# FET_1_and_FET_2_Isolated_Gate_Drive.net
KiCad netlist of a schematic drawn in Altium Designer
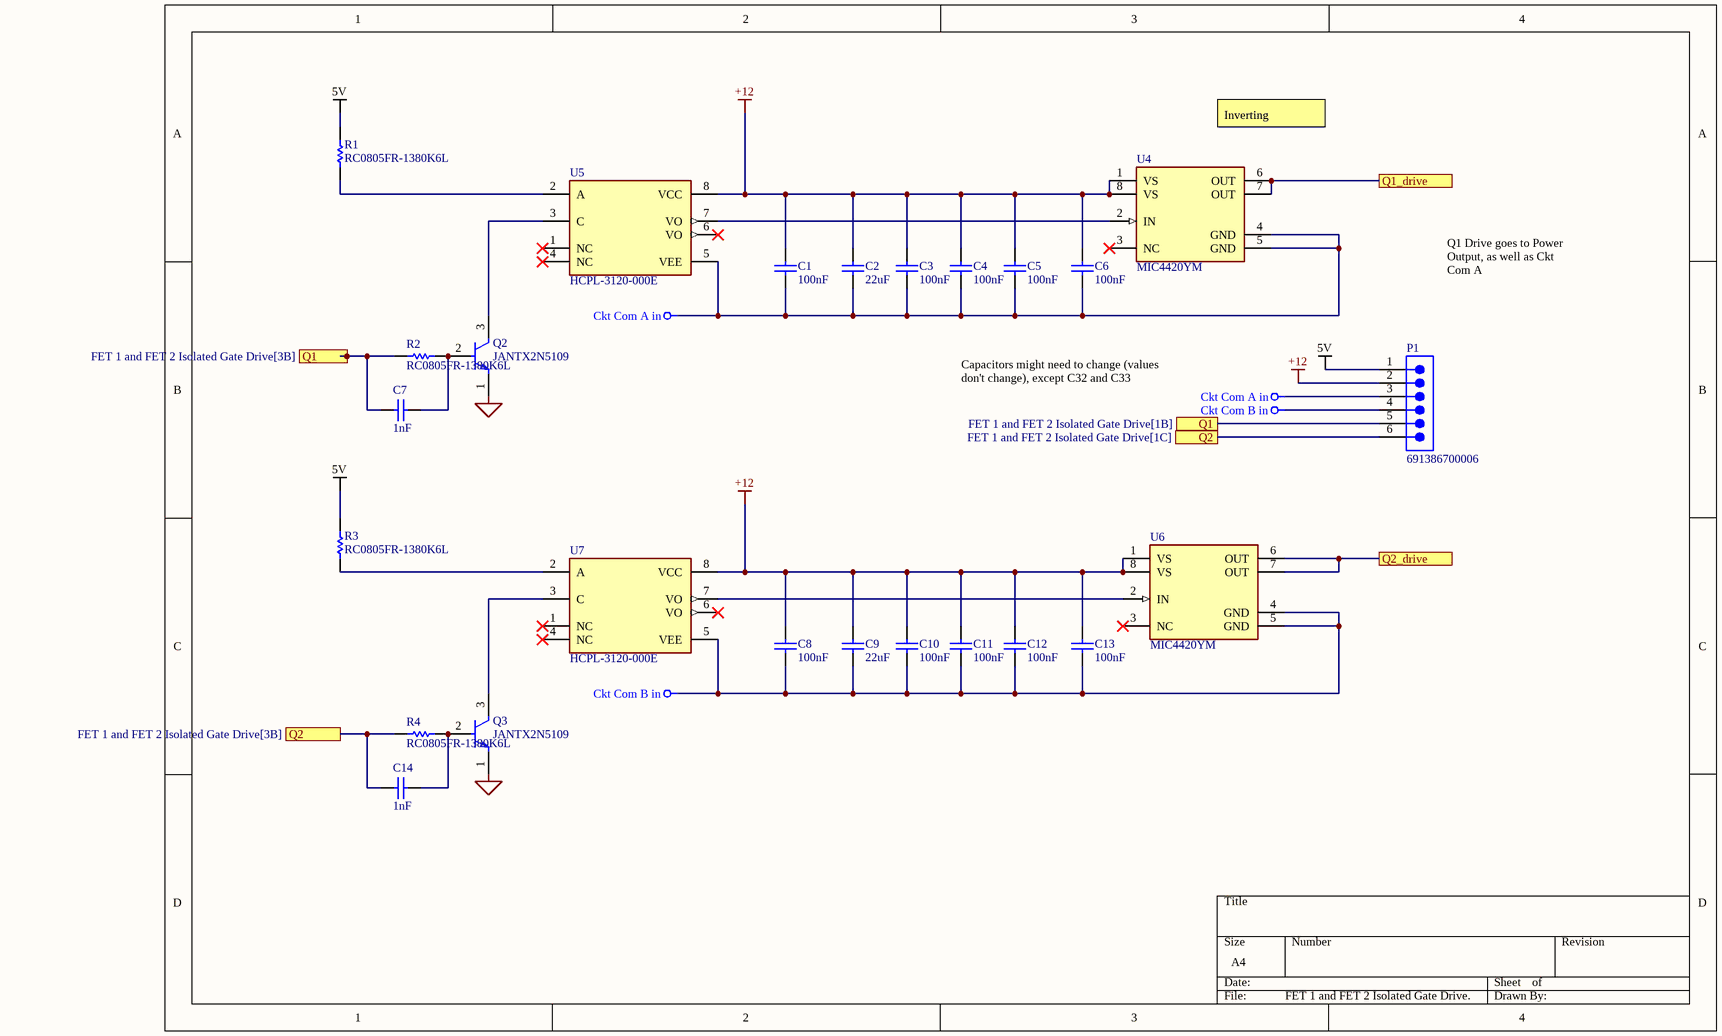
[diagram p0: FET 1 and FET 2 Isolated Gate Drive.SchDoc]

(export (version "E")
  (design (tool "Eeschema 10.0.6"))
  (components
    (comp (ref "C1")
      (value "100nF")
      (footprint "CAPC2013X140X50ML20T25")
      (fields
        (field (name "PART NUMBER") "0805DD104KAT2A")
        (field (name "MANUFACTURER") "AVX Interconnect / Elco")
      )
      (libsource (lib "Altium Content Vault") (part "CAP"))
    )
    (comp (ref "C2")
      (value "22uF")
      (footprint "CAPC0805(2012)145_L")
      (description "CAP 22uF 6.3V ±10% 0805 (2012 Metric) Thickness 1.45mm SMD")
      (fields (field (name "TOLERANCE") "Â±10%"))
      (libsource (lib "Altium Content Vault") (part "CAP"))
    )
    (comp (ref "C3")
      (value "100nF")
      (footprint "CAPC2013X140X50ML20T25")
      (fields
        (field (name "PART NUMBER") "0805DD104KAT2A")
        (field (name "MANUFACTURER") "AVX Interconnect / Elco")
      )
      (libsource (lib "Altium Content Vault") (part "CAP"))
    )
    (comp (ref "C4")
      (value "100nF")
      (footprint "CAPC2013X140X50ML20T25")
      (fields
        (field (name "PART NUMBER") "0805DD104KAT2A")
        (field (name "MANUFACTURER") "AVX Interconnect / Elco")
      )
      (libsource (lib "Altium Content Vault") (part "CAP"))
    )
    (comp (ref "C5")
      (value "100nF")
      (footprint "CAPC2013X140X50ML20T25")
      (fields
        (field (name "PART NUMBER") "0805DD104KAT2A")
        (field (name "MANUFACTURER") "AVX Interconnect / Elco")
      )
      (libsource (lib "Altium Content Vault") (part "CAP"))
    )
    (comp (ref "C6")
      (value "100nF")
      (footprint "CAPC2013X140X50ML20T25")
      (fields
        (field (name "PART NUMBER") "0805DD104KAT2A")
        (field (name "MANUFACTURER") "AVX Interconnect / Elco")
      )
      (libsource (lib "Altium Content Vault") (part "CAP"))
    )
    (comp (ref "C7")
      (value "1nF")
      (footprint "CAPC2013X145X50LL20T20")
      (fields (field (name "PART NUMBER") "VJ0805Y102JXQPW1BC") (field (name "MANUFACTURER") "Vitramon"))
      (libsource (lib "Altium Content Vault") (part "CAP"))
    )
    (comp (ref "C8")
      (value "100nF")
      (footprint "CAPC2013X140X50ML20T25")
      (fields
        (field (name "PART NUMBER") "0805DD104KAT2A")
        (field (name "MANUFACTURER") "AVX Interconnect / Elco")
      )
      (libsource (lib "Altium Content Vault") (part "CAP"))
    )
    (comp (ref "C9")
      (value "22uF")
      (footprint "CAPC0805(2012)145_L")
      (description "CAP 22uF 6.3V ±10% 0805 (2012 Metric) Thickness 1.45mm SMD")
      (fields (field (name "TOLERANCE") "Â±10%"))
      (libsource (lib "Altium Content Vault") (part "CAP"))
    )
    (comp (ref "C10")
      (value "100nF")
      (footprint "CAPC2013X140X50ML20T25")
      (fields
        (field (name "PART NUMBER") "0805DD104KAT2A")
        (field (name "MANUFACTURER") "AVX Interconnect / Elco")
      )
      (libsource (lib "Altium Content Vault") (part "CAP"))
    )
    (comp (ref "C11")
      (value "100nF")
      (footprint "CAPC2013X140X50ML20T25")
      (fields
        (field (name "PART NUMBER") "0805DD104KAT2A")
        (field (name "MANUFACTURER") "AVX Interconnect / Elco")
      )
      (libsource (lib "Altium Content Vault") (part "CAP"))
    )
    (comp (ref "C12")
      (value "100nF")
      (footprint "CAPC2013X140X50ML20T25")
      (fields
        (field (name "PART NUMBER") "0805DD104KAT2A")
        (field (name "MANUFACTURER") "AVX Interconnect / Elco")
      )
      (libsource (lib "Altium Content Vault") (part "CAP"))
    )
    (comp (ref "C13")
      (value "100nF")
      (footprint "CAPC2013X140X50ML20T25")
      (fields
        (field (name "PART NUMBER") "0805DD104KAT2A")
        (field (name "MANUFACTURER") "AVX Interconnect / Elco")
      )
      (libsource (lib "Altium Content Vault") (part "CAP"))
    )
    (comp (ref "C14")
      (value "1nF")
      (footprint "CAPC2013X145X50LL20T20")
      (fields (field (name "PART NUMBER") "VJ0805Y102JXQPW1BC") (field (name "MANUFACTURER") "Vitramon"))
      (libsource (lib "Altium Content Vault") (part "CAP"))
    )
    (comp (ref "P1")
      (value "691386700006")
      (footprint "691386700006")
      (description "Terminal Block, 5.00MM, Male Pcb Horizontal/vertical Cab Divisible, 6 Pins")
      (fields (field (name "VOLTAGE") "300V"))
      (libsource (lib "Altium Content Vault") (part "TBL - 1R - 06P - Male"))
    )
    (comp (ref "Q2")
      (value "JANTX2N5109")
      (footprint "FP-TO-39-MFG")
      (description "TRANS NPN TO39")
      (libsource (lib "Altium Content Vault") (part "a64cbfbad643015290886283bc510aa"))
    )
    (comp (ref "Q3")
      (value "JANTX2N5109")
      (footprint "FP-TO-39-MFG")
      (description "TRANS NPN TO39")
      (libsource (lib "Altium Content Vault") (part "a64cbfbad643015290886283bc510aa"))
    )
    (comp (ref "R1")
      (value "RC0805FR-1380K6L")
      (footprint "RESC2013X60X35NL10T20")
      (fields (field (name "MANUFACTURER") "Yageo"))
      (libsource (lib "Altium Content Vault") (part "RES"))
    )
    (comp (ref "R2")
      (value "RC0805FR-1380K6L")
      (footprint "RESC2013X60X35NL10T20")
      (fields (field (name "MANUFACTURER") "Yageo"))
      (libsource (lib "Altium Content Vault") (part "RES"))
    )
    (comp (ref "R3")
      (value "RC0805FR-1380K6L")
      (footprint "RESC2013X60X35NL10T20")
      (fields (field (name "MANUFACTURER") "Yageo"))
      (libsource (lib "Altium Content Vault") (part "RES"))
    )
    (comp (ref "R4")
      (value "RC0805FR-1380K6L")
      (footprint "RESC2013X60X35NL10T20")
      (fields (field (name "MANUFACTURER") "Yageo"))
      (libsource (lib "Altium Content Vault") (part "RES"))
    )
    (comp (ref "U4")
      (value "MIC4420YM")
      (footprint "FP-SOICN-8LD-PL-1-IPC_C")
      (description "IC GATE DRVR LOW-SIDE 8SOIC")
      (libsource (lib "Altium Content Vault") (part "59696dd0ae0f4050f2c9023f300317a"))
    )
    (comp (ref "U5")
      (value "HCPL-3120-000E")
      (footprint "FP-DIP-8-MFG")
      (description "OPTOISO 3.75KV 1CH GATE DVR 8DIP")
      (fields
        (field (name "MANUFACTURER") "Broadcom")
        (field (name "OCTOPART") "https://octopart.com/hcpl-3120-000e-broadcom-71128428")
      )
      (libsource (lib "Altium Content Vault") (part "c721bc5cd0517253f59fa39a191c1e6"))
    )
    (comp (ref "U6")
      (value "MIC4420YM")
      (footprint "FP-SOICN-8LD-PL-1-IPC_C")
      (description "IC GATE DRVR LOW-SIDE 8SOIC")
      (libsource (lib "Altium Content Vault") (part "59696dd0ae0f4050f2c9023f300317a"))
    )
    (comp (ref "U7")
      (value "HCPL-3120-000E")
      (footprint "FP-DIP-8-MFG")
      (description "OPTOISO 3.75KV 1CH GATE DVR 8DIP")
      (fields
        (field (name "MANUFACTURER") "Broadcom")
        (field (name "OCTOPART") "https://octopart.com/hcpl-3120-000e-broadcom-71128428")
      )
      (libsource (lib "Altium Content Vault") (part "c721bc5cd0517253f59fa39a191c1e6"))
    )
  )
  (nets
    (net (code "1") (name "+12") (class "Default")
      (node (ref "C1") (pin "2") (pinfunction "2_2") (pintype "passive"))
      (node (ref "C10") (pin "2") (pinfunction "2_2") (pintype "passive"))
      (node (ref "C11") (pin "2") (pinfunction "2_2") (pintype "passive"))
      (node (ref "C12") (pin "2") (pinfunction "2_2") (pintype "passive"))
      (node (ref "C13") (pin "2") (pinfunction "2_2") (pintype "passive"))
      (node (ref "C2") (pin "2") (pinfunction "2_2") (pintype "passive"))
      (node (ref "C3") (pin "2") (pinfunction "2_2") (pintype "passive"))
      (node (ref "C4") (pin "2") (pinfunction "2_2") (pintype "passive"))
      (node (ref "C5") (pin "2") (pinfunction "2_2") (pintype "passive"))
      (node (ref "C6") (pin "2") (pinfunction "2_2") (pintype "passive"))
      (node (ref "C8") (pin "2") (pinfunction "2_2") (pintype "passive"))
      (node (ref "C9") (pin "2") (pinfunction "2_2") (pintype "passive"))
      (node (ref "P1") (pin "2") (pinfunction "2_2") (pintype "passive"))
      (node (ref "U4") (pin "1") (pinfunction "VS_1") (pintype "power_in"))
      (node (ref "U4") (pin "8") (pinfunction "VS_8") (pintype "power_in"))
      (node (ref "U5") (pin "8") (pinfunction "VCC_8") (pintype "power_in"))
      (node (ref "U6") (pin "1") (pinfunction "VS_1") (pintype "power_in"))
      (node (ref "U6") (pin "8") (pinfunction "VS_8") (pintype "power_in"))
      (node (ref "U7") (pin "8") (pinfunction "VCC_8") (pintype "power_in"))
    )
    (net (code "2") (name "/Q1") (class "Default")
      (node (ref "C7") (pin "1") (pinfunction "1_1") (pintype "passive"))
      (node (ref "P1") (pin "5") (pinfunction "5_5") (pintype "passive"))
      (node (ref "R2") (pin "2") (pinfunction "2_2") (pintype "passive"))
    )
    (net (code "3") (name "/Q1_drive") (class "Default")
      (node (ref "U4") (pin "6") (pinfunction "OUT_6") (pintype "passive"))
      (node (ref "U4") (pin "7") (pinfunction "OUT_7") (pintype "passive"))
    )
    (net (code "4") (name "/Q2") (class "Default")
      (node (ref "C14") (pin "1") (pinfunction "1_1") (pintype "passive"))
      (node (ref "P1") (pin "6") (pinfunction "6_6") (pintype "passive"))
      (node (ref "R4") (pin "2") (pinfunction "2_2") (pintype "passive"))
    )
    (net (code "5") (name "/Q2_drive") (class "Default")
      (node (ref "U6") (pin "6") (pinfunction "OUT_6") (pintype "passive"))
      (node (ref "U6") (pin "7") (pinfunction "OUT_7") (pintype "passive"))
    )
    (net (code "6") (name "5V") (class "Default")
      (node (ref "P1") (pin "1") (pinfunction "1_1") (pintype "passive"))
      (node (ref "R1") (pin "2") (pinfunction "2_2") (pintype "passive"))
      (node (ref "R3") (pin "2") (pinfunction "2_2") (pintype "passive"))
    )
    (net (code "7") (name "Ckt Com A in") (class "Default")
      (node (ref "C1") (pin "1") (pinfunction "1_1") (pintype "passive"))
      (node (ref "C2") (pin "1") (pinfunction "1_1") (pintype "passive"))
      (node (ref "C3") (pin "1") (pinfunction "1_1") (pintype "passive"))
      (node (ref "C4") (pin "1") (pinfunction "1_1") (pintype "passive"))
      (node (ref "C5") (pin "1") (pinfunction "1_1") (pintype "passive"))
      (node (ref "C6") (pin "1") (pinfunction "1_1") (pintype "passive"))
      (node (ref "P1") (pin "3") (pinfunction "3_3") (pintype "passive"))
      (node (ref "U4") (pin "4") (pinfunction "GND_4") (pintype "power_in"))
      (node (ref "U4") (pin "5") (pinfunction "GND_5") (pintype "power_in"))
      (node (ref "U5") (pin "5") (pinfunction "VEE_5") (pintype "power_in"))
    )
    (net (code "8") (name "Ckt Com B in") (class "Default")
      (node (ref "C10") (pin "1") (pinfunction "1_1") (pintype "passive"))
      (node (ref "C11") (pin "1") (pinfunction "1_1") (pintype "passive"))
      (node (ref "C12") (pin "1") (pinfunction "1_1") (pintype "passive"))
      (node (ref "C13") (pin "1") (pinfunction "1_1") (pintype "passive"))
      (node (ref "C8") (pin "1") (pinfunction "1_1") (pintype "passive"))
      (node (ref "C9") (pin "1") (pinfunction "1_1") (pintype "passive"))
      (node (ref "P1") (pin "4") (pinfunction "4_4") (pintype "passive"))
      (node (ref "U6") (pin "4") (pinfunction "GND_4") (pintype "power_in"))
      (node (ref "U6") (pin "5") (pinfunction "GND_5") (pintype "power_in"))
      (node (ref "U7") (pin "5") (pinfunction "VEE_5") (pintype "power_in"))
    )
    (net (code "9") (name "GND") (class "Default")
      (node (ref "Q2") (pin "1") (pinfunction "E_1") (pintype "passive"))
      (node (ref "Q3") (pin "1") (pinfunction "E_1") (pintype "passive"))
    )
    (net (code "10") (name "Net-(Q2-B)") (class "Default")
      (node (ref "C7") (pin "2") (pinfunction "2_2") (pintype "passive"))
      (node (ref "Q2") (pin "2") (pinfunction "B_2") (pintype "passive"))
      (node (ref "R2") (pin "1") (pinfunction "1_1") (pintype "passive"))
    )
    (net (code "11") (name "Net-(Q2-C)") (class "Default")
      (node (ref "Q2") (pin "3") (pinfunction "C_3") (pintype "passive"))
      (node (ref "U5") (pin "3") (pinfunction "C_3") (pintype "passive"))
    )
    (net (code "12") (name "Net-(Q3-B)") (class "Default")
      (node (ref "C14") (pin "2") (pinfunction "2_2") (pintype "passive"))
      (node (ref "Q3") (pin "2") (pinfunction "B_2") (pintype "passive"))
      (node (ref "R4") (pin "1") (pinfunction "1_1") (pintype "passive"))
    )
    (net (code "13") (name "Net-(Q3-C)") (class "Default")
      (node (ref "Q3") (pin "3") (pinfunction "C_3") (pintype "passive"))
      (node (ref "U7") (pin "3") (pinfunction "C_3") (pintype "passive"))
    )
    (net (code "14") (name "Net-(U4-IN)") (class "Default")
      (node (ref "U4") (pin "2") (pinfunction "IN_2") (pintype "input"))
      (node (ref "U5") (pin "7") (pinfunction "VO_7") (pintype "output"))
    )
    (net (code "15") (name "Net-(U5-A)") (class "Default")
      (node (ref "R1") (pin "1") (pinfunction "1_1") (pintype "passive"))
      (node (ref "U5") (pin "2") (pinfunction "A_2") (pintype "passive"))
    )
    (net (code "16") (name "Net-(U6-IN)") (class "Default")
      (node (ref "U6") (pin "2") (pinfunction "IN_2") (pintype "input"))
      (node (ref "U7") (pin "7") (pinfunction "VO_7") (pintype "output"))
    )
    (net (code "17") (name "Net-(U7-A)") (class "Default")
      (node (ref "R3") (pin "1") (pinfunction "1_1") (pintype "passive"))
      (node (ref "U7") (pin "2") (pinfunction "A_2") (pintype "passive"))
    )
    (net (code "18") (name "unconnected-(U4-NC-Pad3)") (class "Default")
      (node (ref "U4") (pin "3") (pinfunction "NC_3") (pintype "passive+no_connect"))
    )
    (net (code "19") (name "unconnected-(U5-NC-Pad1)") (class "Default")
      (node (ref "U5") (pin "1") (pinfunction "NC_1") (pintype "passive+no_connect"))
    )
    (net (code "20") (name "unconnected-(U5-NC-Pad4)") (class "Default")
      (node (ref "U5") (pin "4") (pinfunction "NC_4") (pintype "passive+no_connect"))
    )
    (net (code "21") (name "unconnected-(U5-VO-Pad6)") (class "Default")
      (node (ref "U5") (pin "6") (pinfunction "VO_6") (pintype "output+no_connect"))
    )
    (net (code "22") (name "unconnected-(U6-NC-Pad3)") (class "Default")
      (node (ref "U6") (pin "3") (pinfunction "NC_3") (pintype "passive+no_connect"))
    )
    (net (code "23") (name "unconnected-(U7-NC-Pad1)") (class "Default")
      (node (ref "U7") (pin "1") (pinfunction "NC_1") (pintype "passive+no_connect"))
    )
    (net (code "24") (name "unconnected-(U7-NC-Pad4)") (class "Default")
      (node (ref "U7") (pin "4") (pinfunction "NC_4") (pintype "passive+no_connect"))
    )
    (net (code "25") (name "unconnected-(U7-VO-Pad6)") (class "Default")
      (node (ref "U7") (pin "6") (pinfunction "VO_6") (pintype "output+no_connect"))
    )
  )
)
